# Sheet2.net
KiCad netlist of a schematic drawn in Altium Designer
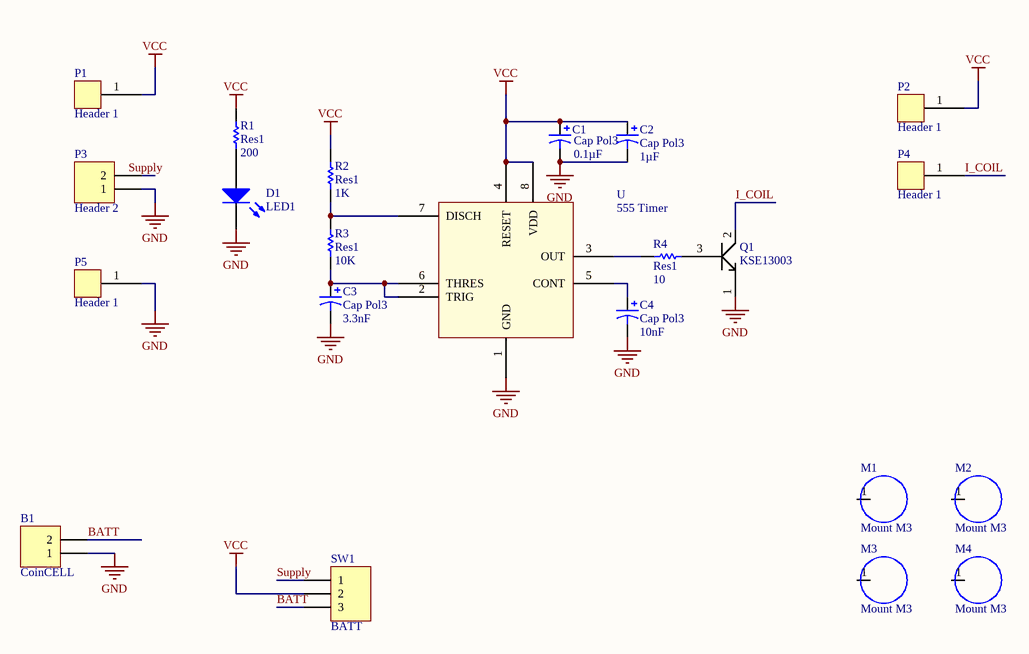
[diagram p0: Sheet2.SchDoc]

(export (version "E")
  (design (tool "Eeschema 10.0.6"))
  (components
    (comp (ref "B1")
      (value "CoinCELL")
      (footprint "COIN")
      (description "Header, 2-Pin")
      (fields (field (name "PUBLISHER") "Altium Limited"))
      (libsource (lib "Miscellaneous Connectors") (part "Header 2"))
    )
    (comp (ref "C1")
      (value "Cap Pol3")
      (footprint "C0805")
      (description "Polarized Capacitor (Surface Mount)")
      (fields (field (name "ALTIUM_VALUE") "0.1µF") (field (name "PUBLISHER") "Altium Limited"))
      (libsource (lib "Miscellaneous Devices") (part "Cap Pol3"))
    )
    (comp (ref "C2")
      (value "Cap Pol3")
      (footprint "C0805")
      (description "Polarized Capacitor (Surface Mount)")
      (fields (field (name "ALTIUM_VALUE") "1µF") (field (name "PUBLISHER") "Altium Limited"))
      (libsource (lib "Miscellaneous Devices") (part "Cap Pol3"))
    )
    (comp (ref "C3")
      (value "Cap Pol3")
      (footprint "C0805")
      (description "Polarized Capacitor (Surface Mount)")
      (fields (field (name "ALTIUM_VALUE") "3.3nF") (field (name "PUBLISHER") "Altium Limited"))
      (libsource (lib "Miscellaneous Devices") (part "Cap Pol3"))
    )
    (comp (ref "C4")
      (value "Cap Pol3")
      (footprint "C0805")
      (description "Polarized Capacitor (Surface Mount)")
      (fields (field (name "ALTIUM_VALUE") "10nF") (field (name "PUBLISHER") "Altium Limited"))
      (libsource (lib "Miscellaneous Devices") (part "Cap Pol3"))
    )
    (comp (ref "D1")
      (value "LED1")
      (footprint "0805")
      (description "Typical RED GaAs LED")
      (fields (field (name "PUBLISHER") "Altium Limited"))
      (libsource (lib "Miscellaneous Devices") (part "LED1"))
    )
    (comp (ref "M1") (value "Mount M3") (libsource (lib "u104Systems") (part "Mount M3")))
    (comp (ref "M2") (value "Mount M3") (libsource (lib "u104Systems") (part "Mount M3")))
    (comp (ref "M3") (value "Mount M3") (libsource (lib "u104Systems") (part "Mount M3")))
    (comp (ref "M4") (value "Mount M3") (libsource (lib "u104Systems") (part "Mount M3")))
    (comp (ref "P1")
      (value "Header 1")
      (footprint "Pad Edge")
      (libsource (lib "u104Systems") (part "Header 1"))
    )
    (comp (ref "P2") (value "Header 1") (footprint "Pad") (libsource (lib "u104Systems") (part "Header 1")))
    (comp (ref "P3")
      (value "Header 2")
      (footprint "Screw Terminal 2-5.08")
      (description "Header, 2-Pin")
      (fields (field (name "PUBLISHER") "Altium Limited"))
      (libsource (lib "Miscellaneous Connectors") (part "Header 2"))
    )
    (comp (ref "P4") (value "Header 1") (footprint "Pad") (libsource (lib "u104Systems") (part "Header 1")))
    (comp (ref "P5")
      (value "Header 1")
      (footprint "Pad Edge")
      (libsource (lib "u104Systems") (part "Header 1"))
    )
    (comp (ref "Q1") (value "KSE13003") (footprint "TO126") (libsource (lib "u104Systems") (part "NPN_ECB")))
    (comp (ref "R1")
      (value "Res1")
      (footprint "0805")
      (description "Resistor")
      (fields (field (name "ALTIUM_VALUE") "200") (field (name "PUBLISHER") "Altium Limited"))
      (libsource (lib "Miscellaneous Devices") (part "Res1"))
    )
    (comp (ref "R2")
      (value "Res1")
      (footprint "0805")
      (description "Resistor")
      (fields (field (name "ALTIUM_VALUE") "1K") (field (name "PUBLISHER") "Altium Limited"))
      (libsource (lib "Miscellaneous Devices") (part "Res1"))
    )
    (comp (ref "R3")
      (value "Res1")
      (footprint "0805")
      (description "Resistor")
      (fields (field (name "ALTIUM_VALUE") "10K") (field (name "PUBLISHER") "Altium Limited"))
      (libsource (lib "Miscellaneous Devices") (part "Res1"))
    )
    (comp (ref "R4")
      (value "Res1")
      (footprint "0805")
      (description "Resistor")
      (fields (field (name "ALTIUM_VALUE") "10") (field (name "PUBLISHER") "Altium Limited"))
      (libsource (lib "Miscellaneous Devices") (part "Res1"))
    )
    (comp (ref "SW1")
      (value "BATT")
      (footprint "Switch SPDT BENT")
      (description "Header, 3-Pin")
      (fields (field (name "PUBLISHER") "Altium Limited"))
      (libsource (lib "Miscellaneous Connectors") (part "Header 3"))
    )
    (comp (ref "U")
      (value "555 Timer")
      (footprint "SOIC8")
      (libsource (lib "u104Systems") (part "555 Timer"))
    )
  )
  (nets
    (net (code "1") (name "/BATT") (class "Default")
      (node (ref "B1") (pin "2") (pinfunction "2_2") (pintype "passive"))
      (node (ref "SW1") (pin "3") (pinfunction "3_3") (pintype "passive"))
    )
    (net (code "2") (name "/I_COIL") (class "Default")
      (node (ref "P4") (pin "1") (pinfunction "1_1") (pintype "passive"))
      (node (ref "Q1") (pin "2") (pinfunction "Coll_2") (pintype "passive"))
    )
    (net (code "3") (name "/Supply") (class "Default")
      (node (ref "SW1") (pin "1") (pinfunction "1_1") (pintype "passive"))
    )
    (net (code "4") (name "GND") (class "Default")
      (node (ref "B1") (pin "1") (pinfunction "1_1") (pintype "passive"))
      (node (ref "C1") (pin "2") (pinfunction "2_2") (pintype "passive"))
      (node (ref "C2") (pin "2") (pinfunction "2_2") (pintype "passive"))
      (node (ref "C3") (pin "2") (pinfunction "2_2") (pintype "passive"))
      (node (ref "C4") (pin "2") (pinfunction "2_2") (pintype "passive"))
      (node (ref "D1") (pin "2") (pinfunction "K_2") (pintype "passive"))
      (node (ref "P3") (pin "1") (pinfunction "1_1") (pintype "passive"))
      (node (ref "P5") (pin "1") (pinfunction "1_1") (pintype "passive"))
      (node (ref "Q1") (pin "1") (pinfunction "Emitter_1") (pintype "passive"))
      (node (ref "U") (pin "1") (pinfunction "GND_1") (pintype "passive"))
    )
    (net (code "5") (name "Net-(D1-A)") (class "Default")
      (node (ref "D1") (pin "1") (pinfunction "A_1") (pintype "passive"))
      (node (ref "R1") (pin "1") (pinfunction "1_1") (pintype "passive"))
    )
    (net (code "6") (name "Net-(Q1-Base)") (class "Default")
      (node (ref "Q1") (pin "3") (pinfunction "Base_3") (pintype "passive"))
      (node (ref "R4") (pin "1") (pinfunction "1_1") (pintype "passive"))
    )
    (net (code "7") (name "Net-(U-CONT)") (class "Default")
      (node (ref "C4") (pin "1") (pinfunction "1_1") (pintype "passive"))
      (node (ref "U") (pin "5") (pinfunction "CONT_5") (pintype "passive"))
    )
    (net (code "8") (name "Net-(U-DISCH)") (class "Default")
      (node (ref "R2") (pin "1") (pinfunction "1_1") (pintype "passive"))
      (node (ref "R3") (pin "2") (pinfunction "2_2") (pintype "passive"))
      (node (ref "U") (pin "7") (pinfunction "DISCH_7") (pintype "passive"))
    )
    (net (code "9") (name "Net-(U-OUT)") (class "Default")
      (node (ref "R4") (pin "2") (pinfunction "2_2") (pintype "passive"))
      (node (ref "U") (pin "3") (pinfunction "OUT_3") (pintype "passive"))
    )
    (net (code "10") (name "Net-(U-THRES)") (class "Default")
      (node (ref "C3") (pin "1") (pinfunction "1_1") (pintype "passive"))
      (node (ref "R3") (pin "1") (pinfunction "1_1") (pintype "passive"))
      (node (ref "U") (pin "2") (pinfunction "TRIG_2") (pintype "passive"))
      (node (ref "U") (pin "6") (pinfunction "THRES_6") (pintype "passive"))
    )
    (net (code "11") (name "VCC") (class "Default")
      (node (ref "C1") (pin "1") (pinfunction "1_1") (pintype "passive"))
      (node (ref "C2") (pin "1") (pinfunction "1_1") (pintype "passive"))
      (node (ref "P1") (pin "1") (pinfunction "1_1") (pintype "passive"))
      (node (ref "P2") (pin "1") (pinfunction "1_1") (pintype "passive"))
      (node (ref "R1") (pin "2") (pinfunction "2_2") (pintype "passive"))
      (node (ref "R2") (pin "2") (pinfunction "2_2") (pintype "passive"))
      (node (ref "SW1") (pin "2") (pinfunction "2_2") (pintype "passive"))
      (node (ref "U") (pin "4") (pinfunction "RESET_4") (pintype "passive"))
      (node (ref "U") (pin "8") (pinfunction "VDD_8") (pintype "passive"))
    )
    (net (code "12") (name "unconnected-(M1-Pad1)") (class "Default")
      (node (ref "M1") (pin "1") (pinfunction "1_1") (pintype "passive"))
    )
    (net (code "13") (name "unconnected-(M2-Pad1)") (class "Default")
      (node (ref "M2") (pin "1") (pinfunction "1_1") (pintype "passive"))
    )
    (net (code "14") (name "unconnected-(M3-Pad1)") (class "Default")
      (node (ref "M3") (pin "1") (pinfunction "1_1") (pintype "passive"))
    )
    (net (code "15") (name "unconnected-(M4-Pad1)") (class "Default")
      (node (ref "M4") (pin "1") (pinfunction "1_1") (pintype "passive"))
    )
    (net (code "16") (name "unconnected-(P3-Pad2)") (class "Default")
      (node (ref "P3") (pin "2") (pinfunction "2_2") (pintype "passive"))
    )
  )
)
